# PWR_P1V8.net
KiCad netlist of a schematic drawn in Altium Designer
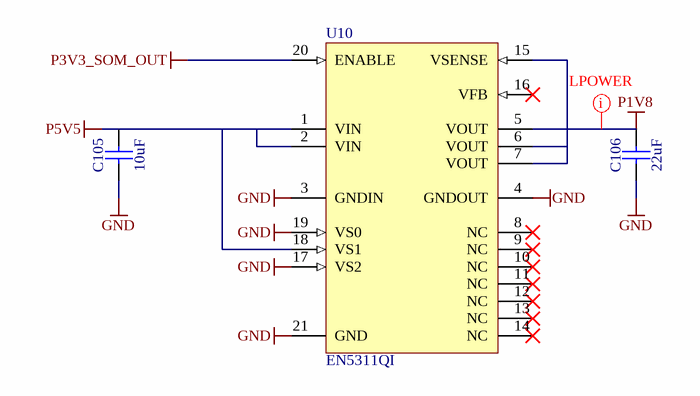
[diagram p0: PWR_P1V8.SchDoc]

(export (version "E")
  (design (tool "Eeschema 10.0.6"))
  (components
    (comp (ref "C105")
      (value "10uF")
      (footprint "CAPC1608X80N")
      (description "Non-polarised capacitor")
      (fields
        (field (name "PART NUMBER") "CC0603_10UF_10V_10%_X5R")
        (field (name "VOLTAGE") "10V")
        (field (name "AUTHOR") "CERN DEM JLC")
      )
      (libsource (lib "Capacitors") (part "Capacitor - non polarized"))
    )
    (comp (ref "C106")
      (value "22uF")
      (footprint "CAPC2012X135N")
      (description "Non-polarised capacitor")
      (fields
        (field (name "PART NUMBER") "CC0805_22UF_16V_10%_X5R")
        (field (name "VOLTAGE") "16V")
        (field (name "AUTHOR") "CERN DEM JLC")
      )
      (libsource (lib "Capacitors") (part "Capacitor - non polarized"))
    )
    (comp (ref "U10") (value "EN5311QI") (footprint "EN5311QI") (libsource (lib "TE") (part "EN5311QI")))
  )
  (nets
    (net (code "1") (name "GND") (class "Default")
      (node (ref "C105") (pin "1") (pinfunction "1_1") (pintype "passive"))
      (node (ref "C106") (pin "1") (pinfunction "1_1") (pintype "passive"))
      (node (ref "U10") (pin "17") (pinfunction "VS2_17") (pintype "input"))
      (node (ref "U10") (pin "19") (pinfunction "VS0_19") (pintype "input"))
      (node (ref "U10") (pin "21") (pinfunction "GND_21") (pintype "power_in"))
      (node (ref "U10") (pin "3") (pinfunction "GNDIN_3") (pintype "power_in"))
      (node (ref "U10") (pin "4") (pinfunction "GNDOUT_4") (pintype "power_in"))
    )
    (net (code "2") (name "P1V8") (class "Default")
      (node (ref "C106") (pin "2") (pinfunction "2_2") (pintype "passive"))
      (node (ref "U10") (pin "15") (pinfunction "VSENSE_15") (pintype "input"))
      (node (ref "U10") (pin "5") (pinfunction "VOUT_5") (pintype "power_in"))
      (node (ref "U10") (pin "6") (pinfunction "VOUT_6") (pintype "power_in"))
      (node (ref "U10") (pin "7") (pinfunction "VOUT_7") (pintype "power_in"))
    )
    (net (code "3") (name "P3V3_SOM_OUT") (class "Default")
      (node (ref "U10") (pin "20") (pinfunction "ENABLE_20") (pintype "input"))
    )
    (net (code "4") (name "P5V5") (class "Default")
      (node (ref "C105") (pin "2") (pinfunction "2_2") (pintype "passive"))
      (node (ref "U10") (pin "1") (pinfunction "VIN_1") (pintype "power_in"))
      (node (ref "U10") (pin "18") (pinfunction "VS1_18") (pintype "input"))
      (node (ref "U10") (pin "2") (pinfunction "VIN_2") (pintype "power_in"))
    )
    (net (code "5") (name "unconnected-(U10-NC-Pad8)") (class "Default")
      (node (ref "U10") (pin "8") (pinfunction "NC_8") (pintype "passive+no_connect"))
    )
    (net (code "6") (name "unconnected-(U10-NC-Pad9)") (class "Default")
      (node (ref "U10") (pin "9") (pinfunction "NC_9") (pintype "passive+no_connect"))
    )
    (net (code "7") (name "unconnected-(U10-NC-Pad10)") (class "Default")
      (node (ref "U10") (pin "10") (pinfunction "NC_10") (pintype "passive+no_connect"))
    )
    (net (code "8") (name "unconnected-(U10-NC-Pad11)") (class "Default")
      (node (ref "U10") (pin "11") (pinfunction "NC_11") (pintype "passive+no_connect"))
    )
    (net (code "9") (name "unconnected-(U10-NC-Pad12)") (class "Default")
      (node (ref "U10") (pin "12") (pinfunction "NC_12") (pintype "passive+no_connect"))
    )
    (net (code "10") (name "unconnected-(U10-NC-Pad13)") (class "Default")
      (node (ref "U10") (pin "13") (pinfunction "NC_13") (pintype "passive+no_connect"))
    )
    (net (code "11") (name "unconnected-(U10-NC-Pad14)") (class "Default")
      (node (ref "U10") (pin "14") (pinfunction "NC_14") (pintype "passive+no_connect"))
    )
    (net (code "12") (name "unconnected-(U10-VFB-Pad16)") (class "Default")
      (node (ref "U10") (pin "16") (pinfunction "VFB_16") (pintype "input+no_connect"))
    )
  )
)
